# tricorder-light-sensors-mk-2_1.net
KiCad netlist of a schematic drawn in EAGLE
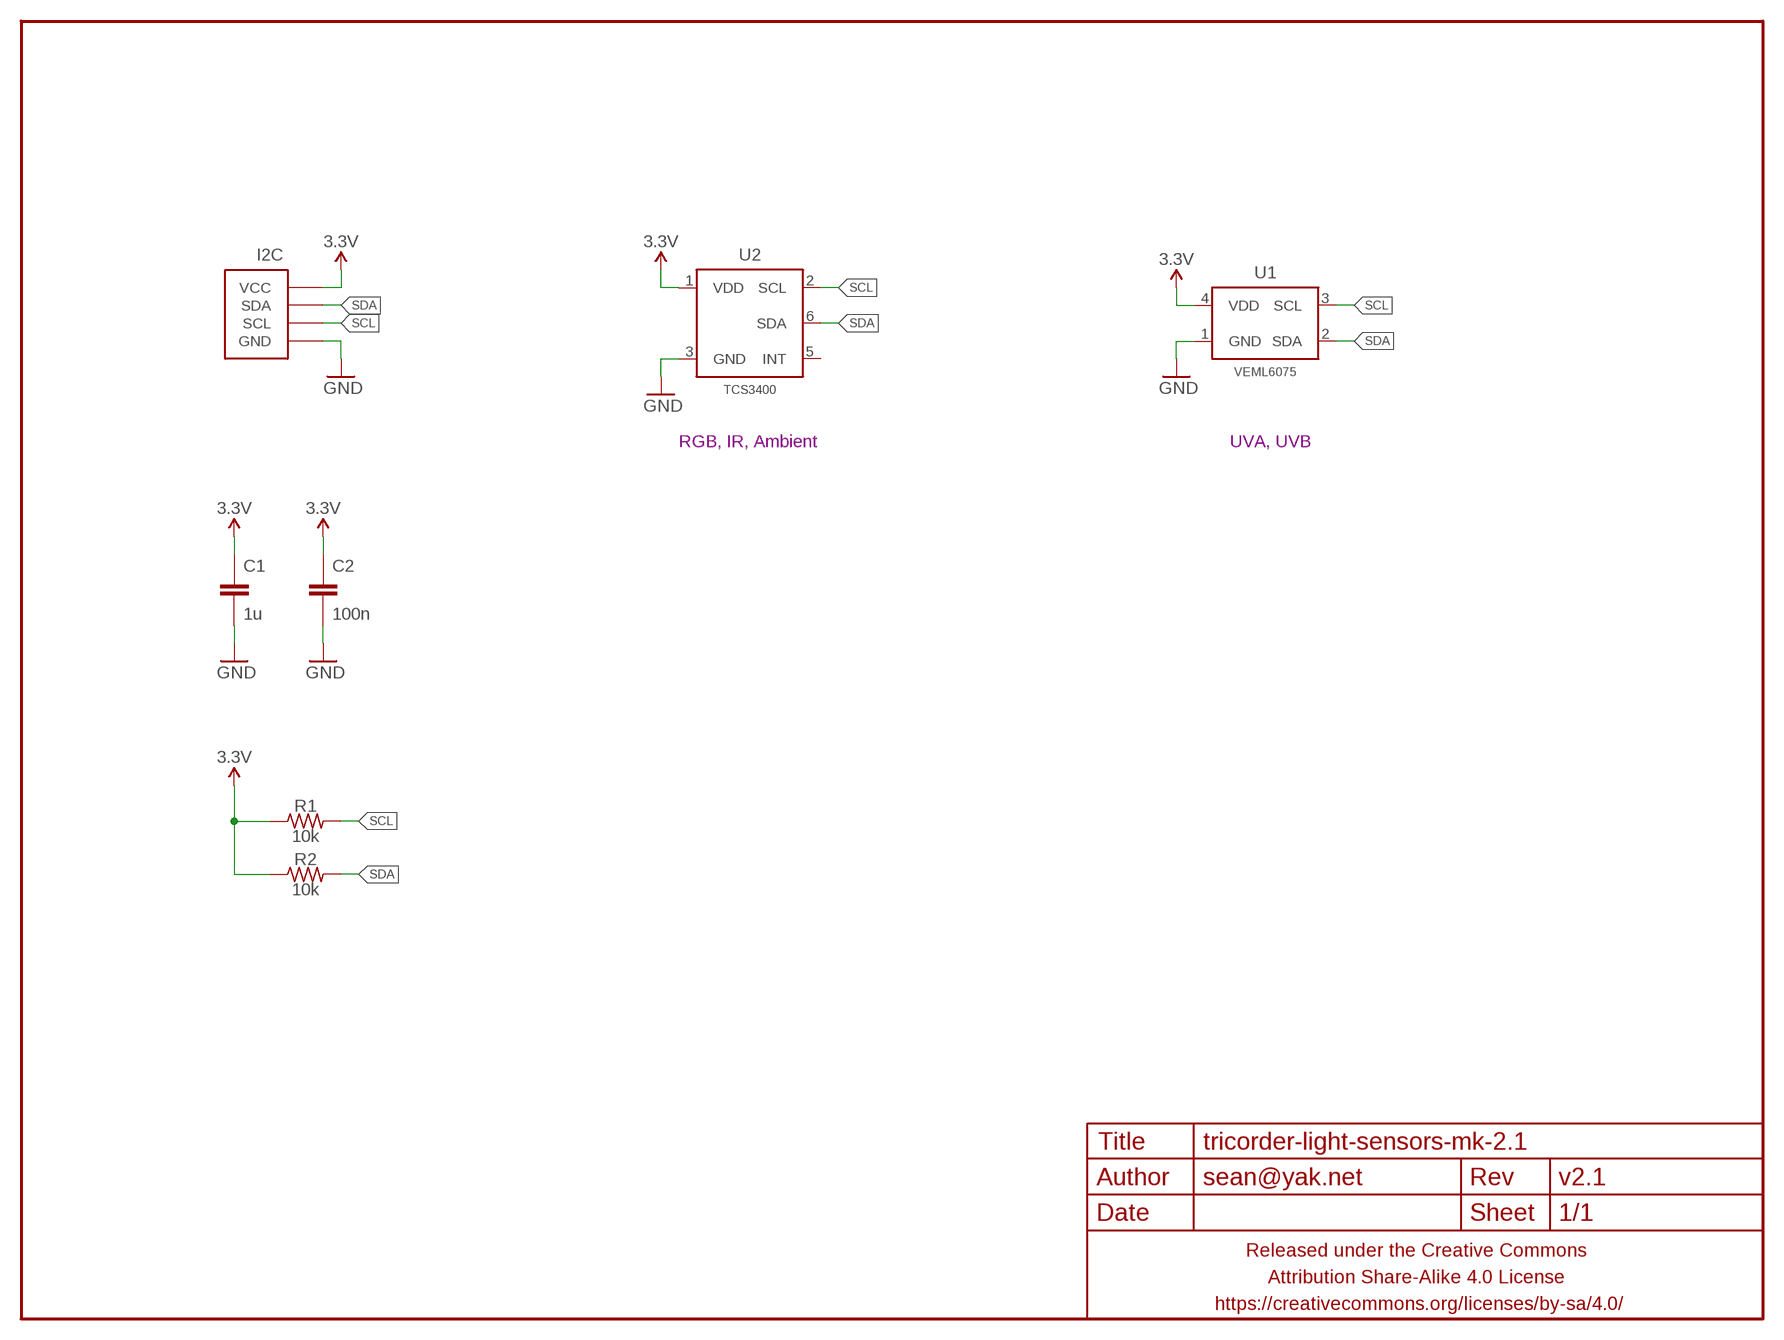
[diagram p0: schematic, sheet 1]

(export (version "E")
  (design (tool "Eeschema 10.0.6"))
  (components
    (comp (ref "C1")
      (value "1u")
      (footprint "eagle-import:C0603")
      (libsource (lib "eagle-import") (part "CAPACITOR-CERAMICC0603"))
    )
    (comp (ref "C2")
      (value "100n")
      (footprint "eagle-import:C0603")
      (libsource (lib "eagle-import") (part "CAPACITOR-CERAMICC0603"))
    )
    (comp (ref "FRAME1")
      (value "FRAME-LETTERNO_PACKAGE")
      (footprint "eagle-import:DUMMY")
      (fields (field (name "DESIGNER") "sean@yak.net") (field (name "VERSION") "v2.1"))
      (libsource (lib "eagle-import") (part "FRAME-LETTERNO_PACKAGE"))
    )
    (comp (ref "I2C")
      (value "M04-I2CPTH-0.1IN-CENTERED")
      (footprint "eagle-import:1X04-PTH-VERT-I2C-CENTERED")
      (libsource (lib "eagle-import") (part "M04-I2CPTH-0.1IN-CENTERED"))
    )
    (comp (ref "R1")
      (value "10k")
      (footprint "eagle-import:R0603")
      (libsource (lib "eagle-import") (part "RESISTORR0603"))
    )
    (comp (ref "R2")
      (value "10k")
      (footprint "eagle-import:R0603")
      (libsource (lib "eagle-import") (part "RESISTORR0603"))
    )
    (comp (ref "U1")
      (value "VEML6075")
      (footprint "eagle-import:OPLGA4")
      (libsource (lib "eagle-import") (part "VEML6075"))
    )
    (comp (ref "U2")
      (value "TCS3400")
      (footprint "eagle-import:TCS3400_DFN6")
      (libsource (lib "eagle-import") (part "TCS3400DFN6"))
    )
  )
  (nets
    (net (code "1") (name "3.3V") (class "Default")
      (node (ref "C1") (pin "1") (pinfunction "1_1") (pintype "passive"))
      (node (ref "C2") (pin "1") (pinfunction "1_1") (pintype "passive"))
      (node (ref "I2C") (pin "VCC") (pinfunction "VCC_VCC") (pintype "bidirectional"))
      (node (ref "R1") (pin "1") (pinfunction "1_1") (pintype "passive"))
      (node (ref "R2") (pin "1") (pinfunction "1_1") (pintype "passive"))
      (node (ref "U1") (pin "4") (pinfunction "VDD_4") (pintype "bidirectional"))
      (node (ref "U2") (pin "1") (pinfunction "VDD_1") (pintype "bidirectional"))
    )
    (net (code "2") (name "GND") (class "Default")
      (node (ref "C1") (pin "2") (pinfunction "2_2") (pintype "passive"))
      (node (ref "C2") (pin "2") (pinfunction "2_2") (pintype "passive"))
      (node (ref "I2C") (pin "GND") (pinfunction "GND_GND") (pintype "bidirectional"))
      (node (ref "U1") (pin "1") (pinfunction "GND_1") (pintype "bidirectional"))
      (node (ref "U2") (pin "3") (pinfunction "GND_3") (pintype "bidirectional"))
    )
    (net (code "3") (name "SCL") (class "Default")
      (node (ref "I2C") (pin "SCL") (pinfunction "SCL_SCL") (pintype "bidirectional"))
      (node (ref "R1") (pin "2") (pinfunction "2_2") (pintype "passive"))
      (node (ref "U1") (pin "3") (pinfunction "SCL_3") (pintype "bidirectional"))
      (node (ref "U2") (pin "2") (pinfunction "SCL_2") (pintype "bidirectional"))
    )
    (net (code "4") (name "SDA") (class "Default")
      (node (ref "I2C") (pin "SDA") (pinfunction "SDA_SDA") (pintype "bidirectional"))
      (node (ref "R2") (pin "2") (pinfunction "2_2") (pintype "passive"))
      (node (ref "U1") (pin "2") (pinfunction "SDA_2") (pintype "bidirectional"))
      (node (ref "U2") (pin "6") (pinfunction "SDA_6") (pintype "bidirectional"))
    )
    (net (code "5") (name "unconnected-(U2-INT-Pad5)") (class "Default")
      (node (ref "U2") (pin "5") (pinfunction "INT_5") (pintype "bidirectional"))
    )
  )
)
